# ProProject_5_1_-__2023-12-06.net
KiCad netlist of a schematic drawn in EasyEDA Pro
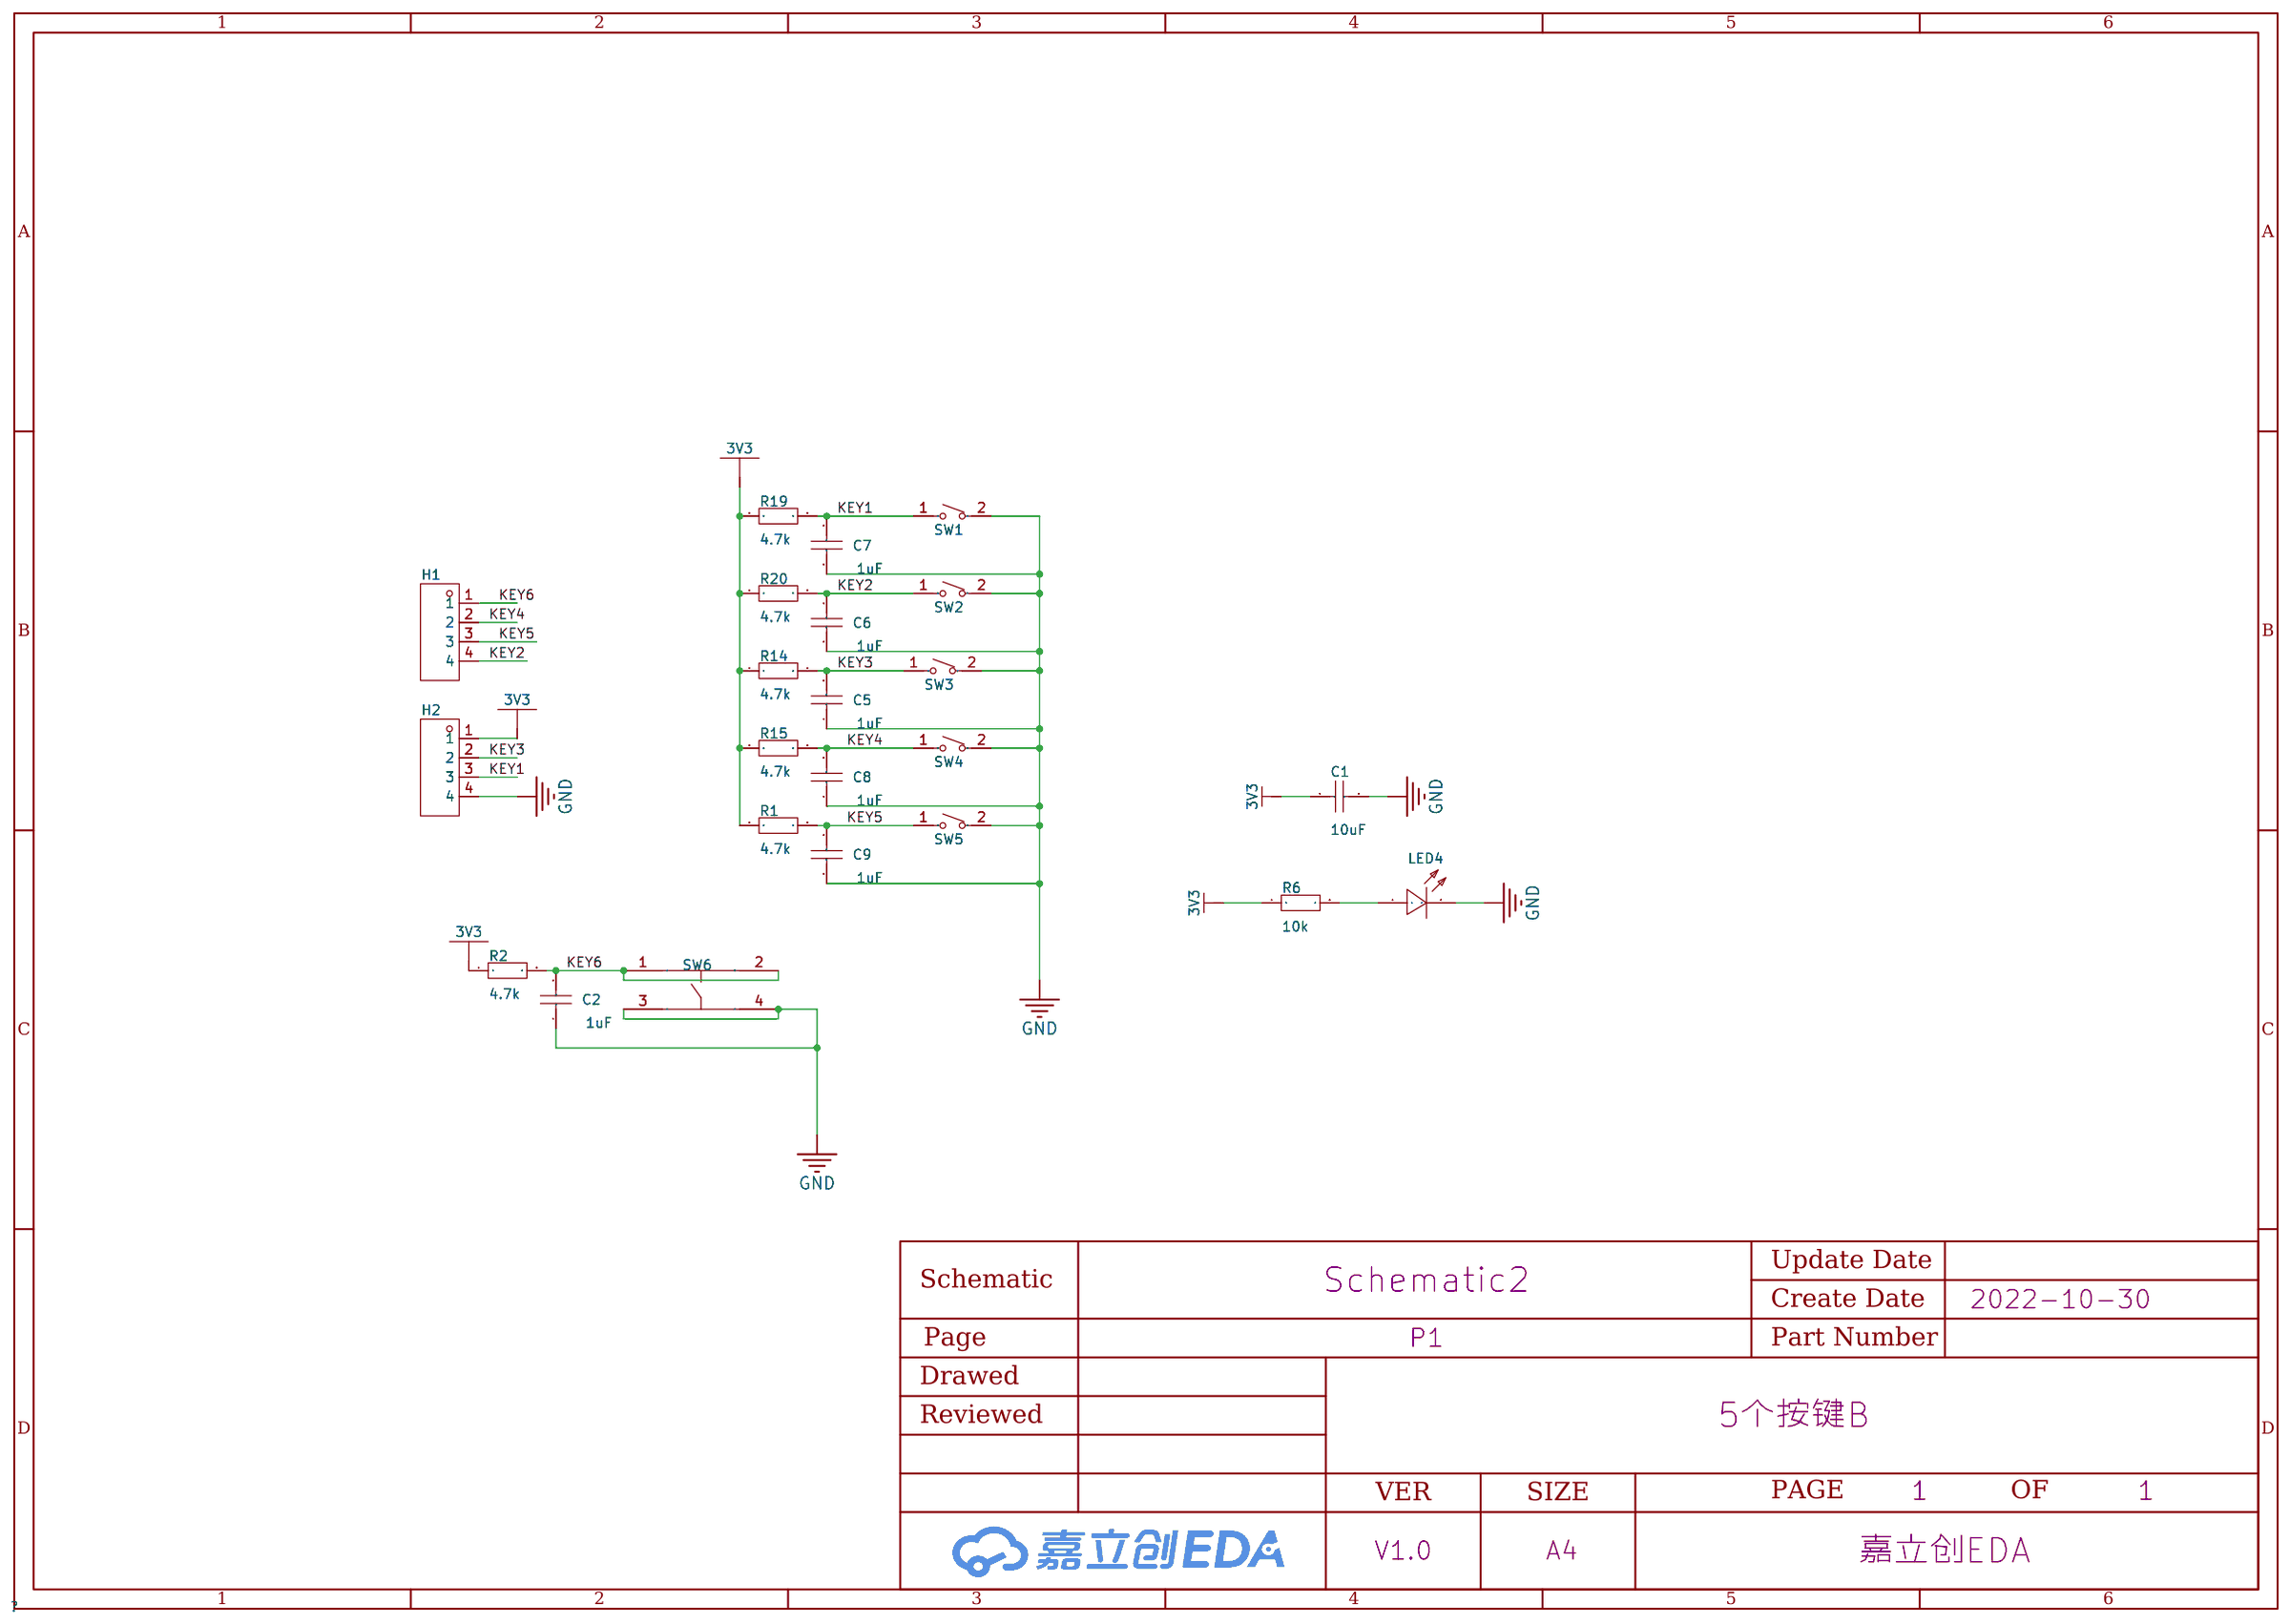
[diagram p0: schematic sheet]

(export (version "E")
  (design (tool "Eeschema 10.0.6"))
  (components
    (comp (ref "C1")
      (value "10uF")
      (footprint "easyedapro:C0805")
      (description "容值:10uF;精度:±10%;额定电压:25V;材质(温度系数):X5R;")
      (fields
        (field (name "Manufacturer Part") "CL21A106KAYNNNE")
        (field (name "Manufacturer") "SAMSUNG(三星)")
      )
      (libsource (lib "easyedapro") (part "CL21A106KAYNNNE"))
    )
    (comp (ref "C2")
      (value "1uF")
      (footprint "easyedapro:C0603")
      (description "容值:1uF;精度:±20%;额定电压:16V;材质(温度系数):Y5V;")
      (fields (field (name "Manufacturer Part") "0603F105M160NT") (field (name "Manufacturer") "FH(风华)"))
      (libsource (lib "easyedapro") (part "0603F105M160NT"))
    )
    (comp (ref "C5")
      (value "1uF")
      (footprint "easyedapro:C0603")
      (description "容值:1uF;精度:±20%;额定电压:16V;材质(温度系数):Y5V;")
      (fields (field (name "Manufacturer Part") "0603F105M160NT") (field (name "Manufacturer") "FH(风华)"))
      (libsource (lib "easyedapro") (part "0603F105M160NT"))
    )
    (comp (ref "C6")
      (value "1uF")
      (footprint "easyedapro:C0603")
      (description "容值:1uF;精度:±20%;额定电压:16V;材质(温度系数):Y5V;")
      (fields (field (name "Manufacturer Part") "0603F105M160NT") (field (name "Manufacturer") "FH(风华)"))
      (libsource (lib "easyedapro") (part "0603F105M160NT"))
    )
    (comp (ref "C7")
      (value "1uF")
      (footprint "easyedapro:C0603")
      (description "容值:1uF;精度:±20%;额定电压:16V;材质(温度系数):Y5V;")
      (fields (field (name "Manufacturer Part") "0603F105M160NT") (field (name "Manufacturer") "FH(风华)"))
      (libsource (lib "easyedapro") (part "0603F105M160NT"))
    )
    (comp (ref "C8")
      (value "1uF")
      (footprint "easyedapro:C0603")
      (description "容值:1uF;精度:±20%;额定电压:16V;材质(温度系数):Y5V;")
      (fields (field (name "Manufacturer Part") "0603F105M160NT") (field (name "Manufacturer") "FH(风华)"))
      (libsource (lib "easyedapro") (part "0603F105M160NT"))
    )
    (comp (ref "C9")
      (value "1uF")
      (footprint "easyedapro:C0603")
      (description "容值:1uF;精度:±20%;额定电压:16V;材质(温度系数):Y5V;")
      (fields (field (name "Manufacturer Part") "0603F105M160NT") (field (name "Manufacturer") "FH(风华)"))
      (libsource (lib "easyedapro") (part "0603F105M160NT"))
    )
    (comp (ref "H1")
      (value "~")
      (footprint "easyedapro:HDR-TH_4P-P2.54-V-F")
      (libsource (lib "easyedapro") (part "2.54-1*4P母"))
    )
    (comp (ref "H2")
      (value "~")
      (footprint "easyedapro:HDR-TH_4P-P2.54-V-F")
      (libsource (lib "easyedapro") (part "2.54-1*4P母"))
    )
    (comp (ref "LED4")
      (value "KT-0603R")
      (footprint "easyedapro:LED0603-R-RD")
      (fields (field (name "Manufacturer") "KENTO"))
      (libsource (lib "easyedapro") (part "KT-0603R"))
    )
    (comp (ref "R1")
      (value "4.7k")
      (footprint "easyedapro:R0603_3")
      (description "电阻类型:厚膜电阻;阻值:4.7k;精度:±1%;功率:1/10W;温度系数:±100ppm/;最大工作电压:75V;工作温度范围:-55~+155;")
      (fields
        (field (name "Manufacturer Part") "0603WAF4701T5E")
        (field (name "Manufacturer") "UNI-ROYAL(厚声)")
      )
      (libsource (lib "easyedapro") (part "0603WAF4701T5E"))
    )
    (comp (ref "R2")
      (value "4.7k")
      (footprint "easyedapro:R0603_3")
      (description "电阻类型:厚膜电阻;阻值:4.7k;精度:±1%;功率:1/10W;温度系数:±100ppm/;最大工作电压:75V;工作温度范围:-55~+155;")
      (fields
        (field (name "Manufacturer Part") "0603WAF4701T5E")
        (field (name "Manufacturer") "UNI-ROYAL(厚声)")
      )
      (libsource (lib "easyedapro") (part "0603WAF4701T5E"))
    )
    (comp (ref "R6")
      (value "10k")
      (footprint "easyedapro:R0603")
      (description "电阻类型:厚膜电阻;阻值:10k;精度:±1%;功率:1/10W;温度系数:±100ppm/;最大工作电压:75V;工作温度范围:-55~+155;")
      (fields
        (field (name "Manufacturer Part") "0603WAF1002T5E")
        (field (name "Manufacturer") "UNI-ROYAL(厚声)")
      )
      (libsource (lib "easyedapro") (part "0603WAF1002T5E"))
    )
    (comp (ref "R14")
      (value "4.7k")
      (footprint "easyedapro:R0603_3")
      (description "电阻类型:厚膜电阻;阻值:4.7k;精度:±1%;功率:1/10W;温度系数:±100ppm/;最大工作电压:75V;工作温度范围:-55~+155;")
      (fields
        (field (name "Manufacturer Part") "0603WAF4701T5E")
        (field (name "Manufacturer") "UNI-ROYAL(厚声)")
      )
      (libsource (lib "easyedapro") (part "0603WAF4701T5E"))
    )
    (comp (ref "R15")
      (value "4.7k")
      (footprint "easyedapro:R0603_3")
      (description "电阻类型:厚膜电阻;阻值:4.7k;精度:±1%;功率:1/10W;温度系数:±100ppm/;最大工作电压:75V;工作温度范围:-55~+155;")
      (fields
        (field (name "Manufacturer Part") "0603WAF4701T5E")
        (field (name "Manufacturer") "UNI-ROYAL(厚声)")
      )
      (libsource (lib "easyedapro") (part "0603WAF4701T5E"))
    )
    (comp (ref "R19")
      (value "4.7k")
      (footprint "easyedapro:R0603_3")
      (description "电阻类型:厚膜电阻;阻值:4.7k;精度:±1%;功率:1/10W;温度系数:±100ppm/;最大工作电压:75V;工作温度范围:-55~+155;")
      (fields
        (field (name "Manufacturer Part") "0603WAF4701T5E")
        (field (name "Manufacturer") "UNI-ROYAL(厚声)")
      )
      (libsource (lib "easyedapro") (part "0603WAF4701T5E"))
    )
    (comp (ref "R20")
      (value "4.7k")
      (footprint "easyedapro:R0603_3")
      (description "电阻类型:厚膜电阻;阻值:4.7k;精度:±1%;功率:1/10W;温度系数:±100ppm/;最大工作电压:75V;工作温度范围:-55~+155;")
      (fields
        (field (name "Manufacturer Part") "0603WAF4701T5E")
        (field (name "Manufacturer") "UNI-ROYAL(厚声)")
      )
      (libsource (lib "easyedapro") (part "0603WAF4701T5E"))
    )
    (comp (ref "SW1")
      (value "GT-TC141A-H050-L1")
      (footprint "easyedapro:SW-TH_L6.0-W6.0-P5.00")
      (fields (field (name "Manufacturer") "G-Switch(品赞)"))
      (libsource (lib "easyedapro") (part "GT-TC141A-H050-L1"))
    )
    (comp (ref "SW2")
      (value "GT-TC141A-H050-L1")
      (footprint "easyedapro:SW-TH_L6.0-W6.0-P5.00")
      (fields (field (name "Manufacturer") "G-Switch(品赞)"))
      (libsource (lib "easyedapro") (part "GT-TC141A-H050-L1"))
    )
    (comp (ref "SW3")
      (value "GT-TC141A-H050-L1")
      (footprint "easyedapro:SW-TH_L6.0-W6.0-P5.00")
      (fields (field (name "Manufacturer") "G-Switch(品赞)"))
      (libsource (lib "easyedapro") (part "GT-TC141A-H050-L1"))
    )
    (comp (ref "SW4")
      (value "GT-TC141A-H050-L1")
      (footprint "easyedapro:SW-TH_L6.0-W6.0-P5.00")
      (fields (field (name "Manufacturer") "G-Switch(品赞)"))
      (libsource (lib "easyedapro") (part "GT-TC141A-H050-L1"))
    )
    (comp (ref "SW5")
      (value "GT-TC141A-H050-L1")
      (footprint "easyedapro:SW-TH_L6.0-W6.0-P5.00")
      (fields (field (name "Manufacturer") "G-Switch(品赞)"))
      (libsource (lib "easyedapro") (part "GT-TC141A-H050-L1"))
    )
    (comp (ref "SW6")
      (value "PTS810SJM250SMTRLFS")
      (footprint "easyedapro:KEY-SMD_4P-L4.2-W3.2-P2.20-LS4.6")
      (description "触点电流:50mA;额定电压(DC):16V;电路结构:单刀单掷;安装方式:立贴;按钮形状:圆形按钮;带灯:-;开关长度:4.2mm;开关宽度:3.2mm;开关高度:2.5mm;")
      (fields (field (name "Manufacturer") "C&K"))
      (libsource (lib "easyedapro") (part "PTS810SJM250SMTRLFS"))
    )
  )
  (nets
    (net (code "1") (name "/KEY1") (class "Default")
      (node (ref "C7") (pin "2") (pinfunction "2_2") (pintype "input"))
      (node (ref "H2") (pin "3") (pinfunction "3_3") (pintype "input"))
      (node (ref "R19") (pin "2") (pinfunction "2_2") (pintype "input"))
      (node (ref "SW1") (pin "1") (pinfunction "1_1") (pintype "input"))
    )
    (net (code "2") (name "/KEY2") (class "Default")
      (node (ref "C6") (pin "2") (pinfunction "2_2") (pintype "input"))
      (node (ref "H1") (pin "4") (pinfunction "4_4") (pintype "input"))
      (node (ref "R20") (pin "2") (pinfunction "2_2") (pintype "input"))
      (node (ref "SW2") (pin "1") (pinfunction "1_1") (pintype "input"))
    )
    (net (code "3") (name "/KEY3") (class "Default")
      (node (ref "C5") (pin "2") (pinfunction "2_2") (pintype "input"))
      (node (ref "H2") (pin "2") (pinfunction "2_2") (pintype "input"))
      (node (ref "R14") (pin "2") (pinfunction "2_2") (pintype "input"))
      (node (ref "SW3") (pin "1") (pinfunction "1_1") (pintype "input"))
    )
    (net (code "4") (name "/KEY4") (class "Default")
      (node (ref "C8") (pin "2") (pinfunction "2_2") (pintype "input"))
      (node (ref "H1") (pin "2") (pinfunction "2_2") (pintype "input"))
      (node (ref "R15") (pin "2") (pinfunction "2_2") (pintype "input"))
      (node (ref "SW4") (pin "1") (pinfunction "1_1") (pintype "input"))
    )
    (net (code "5") (name "/KEY5") (class "Default")
      (node (ref "C9") (pin "2") (pinfunction "2_2") (pintype "input"))
      (node (ref "H1") (pin "3") (pinfunction "3_3") (pintype "input"))
      (node (ref "R1") (pin "2") (pinfunction "2_2") (pintype "input"))
      (node (ref "SW5") (pin "1") (pinfunction "1_1") (pintype "input"))
    )
    (net (code "6") (name "/KEY6") (class "Default")
      (node (ref "C2") (pin "2") (pinfunction "2_2") (pintype "input"))
      (node (ref "H1") (pin "1") (pinfunction "1_1") (pintype "input"))
      (node (ref "R2") (pin "2") (pinfunction "2_2") (pintype "input"))
      (node (ref "SW6") (pin "1") (pinfunction "1_1") (pintype "input"))
      (node (ref "SW6") (pin "2") (pinfunction "2_2") (pintype "input"))
    )
    (net (code "7") (name "3V3") (class "Default")
      (node (ref "C1") (pin "2") (pinfunction "2_2") (pintype "input"))
      (node (ref "H2") (pin "1") (pinfunction "1_1") (pintype "input"))
      (node (ref "R1") (pin "1") (pinfunction "1_1") (pintype "input"))
      (node (ref "R14") (pin "1") (pinfunction "1_1") (pintype "input"))
      (node (ref "R15") (pin "1") (pinfunction "1_1") (pintype "input"))
      (node (ref "R19") (pin "1") (pinfunction "1_1") (pintype "input"))
      (node (ref "R2") (pin "1") (pinfunction "1_1") (pintype "input"))
      (node (ref "R20") (pin "1") (pinfunction "1_1") (pintype "input"))
      (node (ref "R6") (pin "1") (pinfunction "1_1") (pintype "input"))
    )
    (net (code "8") (name "GND") (class "Default")
      (node (ref "C1") (pin "1") (pinfunction "1_1") (pintype "input"))
      (node (ref "C2") (pin "1") (pinfunction "1_1") (pintype "input"))
      (node (ref "C5") (pin "1") (pinfunction "1_1") (pintype "input"))
      (node (ref "C6") (pin "1") (pinfunction "1_1") (pintype "input"))
      (node (ref "C7") (pin "1") (pinfunction "1_1") (pintype "input"))
      (node (ref "C8") (pin "1") (pinfunction "1_1") (pintype "input"))
      (node (ref "C9") (pin "1") (pinfunction "1_1") (pintype "input"))
      (node (ref "H2") (pin "4") (pinfunction "4_4") (pintype "input"))
      (node (ref "LED4") (pin "2") (pinfunction "K_2") (pintype "input"))
      (node (ref "SW1") (pin "2") (pinfunction "2_2") (pintype "input"))
      (node (ref "SW2") (pin "2") (pinfunction "2_2") (pintype "input"))
      (node (ref "SW3") (pin "2") (pinfunction "2_2") (pintype "input"))
      (node (ref "SW4") (pin "2") (pinfunction "2_2") (pintype "input"))
      (node (ref "SW5") (pin "2") (pinfunction "2_2") (pintype "input"))
      (node (ref "SW6") (pin "3") (pinfunction "3_3") (pintype "input"))
      (node (ref "SW6") (pin "4") (pinfunction "4_4") (pintype "input"))
    )
    (net (code "9") (name "Net-(LED4-A)") (class "Default")
      (node (ref "LED4") (pin "1") (pinfunction "A_1") (pintype "input"))
      (node (ref "R6") (pin "2") (pinfunction "2_2") (pintype "input"))
    )
  )
)
